# 1_STM32F103C8-core.net
KiCad netlist of a schematic drawn in Altium Designer
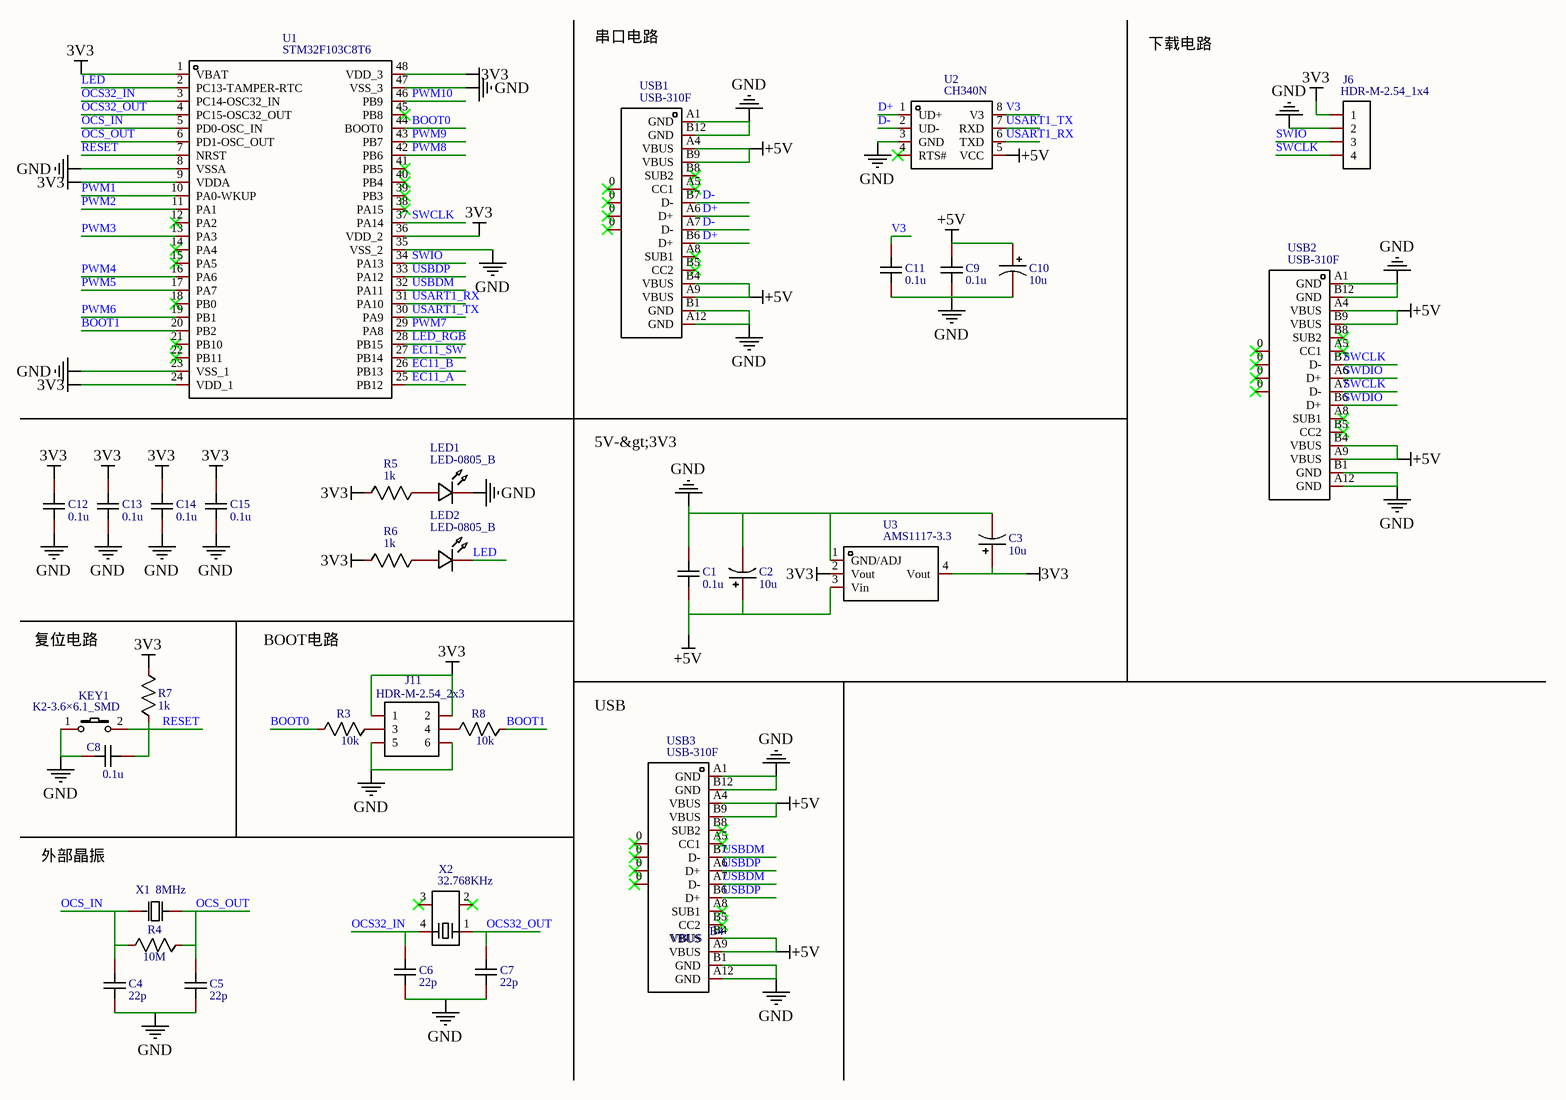
[diagram p0: 1_STM32F103C8-core.schdoc]

(export (version "E")
  (design (tool "Eeschema 10.0.6"))
  (components
    (comp (ref "C1")
      (value "0.1u")
      (fields (field (name "NAME") "0.1u"))
      (libsource (lib "altium-import") (part "root_1_0.1u_"))
    )
    (comp (ref "C2")
      (value "10u")
      (fields (field (name "NAME") "10u"))
      (libsource (lib "altium-import") (part "root_1_10u_"))
    )
    (comp (ref "C3")
      (value "10u")
      (fields (field (name "NAME") "10u"))
      (libsource (lib "altium-import") (part "root_1_10u_"))
    )
    (comp (ref "C4")
      (value "22p")
      (fields (field (name "NAME") "22p"))
      (libsource (lib "altium-import") (part "root_1_22p_"))
    )
    (comp (ref "C5")
      (value "22p")
      (fields (field (name "NAME") "22p"))
      (libsource (lib "altium-import") (part "root_1_22p_"))
    )
    (comp (ref "C6")
      (value "22p")
      (fields (field (name "NAME") "22p"))
      (libsource (lib "altium-import") (part "root_1_22p_"))
    )
    (comp (ref "C7")
      (value "22p")
      (fields (field (name "NAME") "22p"))
      (libsource (lib "altium-import") (part "root_1_22p_"))
    )
    (comp (ref "C8")
      (value "0.1u")
      (fields (field (name "NAME") "0.1u"))
      (libsource (lib "altium-import") (part "root_2_0.1u_"))
    )
    (comp (ref "C9")
      (value "0.1u")
      (fields (field (name "NAME") "0.1u"))
      (libsource (lib "altium-import") (part "root_1_0.1u_"))
    )
    (comp (ref "C10")
      (value "10u")
      (fields (field (name "NAME") "10u"))
      (libsource (lib "altium-import") (part "root_3_10u_"))
    )
    (comp (ref "C11")
      (value "0.1u")
      (fields (field (name "NAME") "0.1u"))
      (libsource (lib "altium-import") (part "root_1_0.1u_"))
    )
    (comp (ref "C12")
      (value "0.1u")
      (fields (field (name "NAME") "0.1u"))
      (libsource (lib "altium-import") (part "root_1_0.1u_"))
    )
    (comp (ref "C13")
      (value "0.1u")
      (fields (field (name "NAME") "0.1u"))
      (libsource (lib "altium-import") (part "root_1_0.1u_"))
    )
    (comp (ref "C14")
      (value "0.1u")
      (fields (field (name "NAME") "0.1u"))
      (libsource (lib "altium-import") (part "root_1_0.1u_"))
    )
    (comp (ref "C15")
      (value "0.1u")
      (fields (field (name "NAME") "0.1u"))
      (libsource (lib "altium-import") (part "root_1_0.1u_"))
    )
    (comp (ref "J6")
      (value "HDR-M-2.54_1x4")
      (fields (field (name "NAME") "HDR-M-2.54_1x4"))
      (libsource (lib "altium-import") (part "root_0_HDR-M-2.54_1x4_"))
    )
    (comp (ref "J11")
      (value "HDR-M-2.54_2x3")
      (fields (field (name "NAME") "HDR-M-2.54_2x3"))
      (libsource (lib "altium-import") (part "root_0_HDR-M-2.54_2x3_"))
    )
    (comp (ref "KEY1")
      (value "K2-3.6×6.1_SMD")
      (fields (field (name "NAME") "K2-3.6×6.1_SMD") (field (name "MANUFACTURER PART") "K2-1107ST-A4SW-06"))
      (libsource (lib "altium-import") (part "root_0_K2-1107ST-A4SW-06_"))
    )
    (comp (ref "LED1")
      (value "LED-0805_B")
      (fields
        (field (name "NAME") "LED-0805_B")
        (field (name "MANUFACTURER") "方舟 ARKLED")
        (field (name "MANUFACTURER PART") "D-B080508B1-KS2")
      )
      (libsource (lib "altium-import") (part "root_0_D-B080508B1-KS2_"))
    )
    (comp (ref "LED2")
      (value "LED-0805_B")
      (fields
        (field (name "NAME") "LED-0805_B")
        (field (name "MANUFACTURER") "方舟 ARKLED")
        (field (name "MANUFACTURER PART") "D-B080508B1-KS2")
      )
      (libsource (lib "altium-import") (part "root_0_D-B080508B1-KS2_"))
    )
    (comp (ref "R3")
      (value "10k")
      (fields (field (name "NAME") "10k"))
      (libsource (lib "altium-import") (part "root_0_10k_"))
    )
    (comp (ref "R4")
      (value "10M")
      (fields (field (name "NAME") "10M"))
      (libsource (lib "altium-import") (part "root_0_10M_"))
    )
    (comp (ref "R5")
      (value "1k")
      (fields (field (name "NAME") "1k"))
      (libsource (lib "altium-import") (part "root_0_1k_"))
    )
    (comp (ref "R6")
      (value "1k")
      (fields (field (name "NAME") "1k"))
      (libsource (lib "altium-import") (part "root_0_1k_"))
    )
    (comp (ref "R7")
      (value "1k")
      (fields (field (name "NAME") "1k"))
      (libsource (lib "altium-import") (part "root_1_1k_"))
    )
    (comp (ref "R8")
      (value "10k")
      (fields (field (name "NAME") "10k"))
      (libsource (lib "altium-import") (part "root_0_10k_"))
    )
    (comp (ref "U1")
      (value "STM32F103C8T6")
      (fields (field (name "NAME") "STM32F103C8T6") (field (name "MANUFACTURER") "STMicroelectronics"))
      (libsource (lib "altium-import") (part "root_0_STM32F103C8T6_"))
    )
    (comp (ref "U2")
      (value "CH340N")
      (fields (field (name "NAME") "CH340N"))
      (libsource (lib "altium-import") (part "root_0_CH340N_"))
    )
    (comp (ref "U3")
      (value "AMS1117-3.3")
      (fields (field (name "NAME") "AMS1117-3.3") (field (name "MANUFACTURER") "AMS"))
      (libsource (lib "altium-import") (part "root_0_AMS1117-3.3_"))
    )
    (comp (ref "USB1")
      (value "USB-310F")
      (fields (field (name "NAME") "USB-310F") (field (name "MANUFACTURER") "HOOYA"))
      (libsource (lib "altium-import") (part "root_0_USB-310F_"))
    )
    (comp (ref "USB2")
      (value "USB-310F")
      (fields (field (name "NAME") "USB-310F") (field (name "MANUFACTURER") "HOOYA"))
      (libsource (lib "altium-import") (part "root_0_USB-310F_"))
    )
    (comp (ref "USB3")
      (value "USB-310F")
      (fields
        (field (name "NAME") "USB-310F")
        (field (name "MANUFACTURER") "HOOYA")
        (field (name "NUMBER") "B4")
        (field (name "NAME_1") "VBUS")
      )
      (libsource (lib "altium-import") (part "root_0_USB-310F_"))
    )
    (comp (ref "X1")
      (value "8MHz")
      (description "频率:8MHz;频率公差:±20ppm;频率稳定度:±30ppm;负载电容:16pF;")
      (fields
        (field (name "NAME") "8MHz")
        (field (name "MANUFACTURER") "JYJE(晶友嘉)")
        (field (name "MANUFACTURER PART") "S1C80000VWGAC")
      )
      (libsource (lib "altium-import") (part "root_0_S1C80000VWGAC_"))
    )
    (comp (ref "X2")
      (value "32.768KHz")
      (fields
        (field (name "NAME") "32.768KHz")
        (field (name "MANUFACTURER PART") "Q13MC3061000300")
        (field (name "MANUFACTURER") "EPSON")
      )
      (libsource (lib "altium-import") (part "root_1_Q13MC3061000300_"))
    )
  )
  (nets
    (net (code "1") (name "+5V") (class "Default")
      (node (ref "C1") (pin "1") (pinfunction "1_1") (pintype "passive"))
      (node (ref "C10") (pin "1") (pinfunction "1_1") (pintype "passive"))
      (node (ref "C2") (pin "1") (pinfunction "1_1") (pintype "passive"))
      (node (ref "C9") (pin "2") (pinfunction "2_2") (pintype "passive"))
      (node (ref "U2") (pin "5") (pinfunction "VCC_5") (pintype "passive"))
      (node (ref "U3") (pin "3") (pinfunction "Vin_3") (pintype "passive"))
      (node (ref "USB1") (pin "A4") (pinfunction "VBUS_A4") (pintype "passive"))
      (node (ref "USB1") (pin "A9") (pinfunction "VBUS_A9") (pintype "passive"))
      (node (ref "USB1") (pin "B4") (pinfunction "VBUS_B4") (pintype "passive"))
      (node (ref "USB1") (pin "B9") (pinfunction "VBUS_B9") (pintype "passive"))
      (node (ref "USB2") (pin "A4") (pinfunction "VBUS_A4") (pintype "passive"))
      (node (ref "USB2") (pin "A9") (pinfunction "VBUS_A9") (pintype "passive"))
      (node (ref "USB2") (pin "B4") (pinfunction "VBUS_B4") (pintype "passive"))
      (node (ref "USB2") (pin "B9") (pinfunction "VBUS_B9") (pintype "passive"))
      (node (ref "USB3") (pin "A4") (pinfunction "VBUS_A4") (pintype "passive"))
      (node (ref "USB3") (pin "A9") (pinfunction "VBUS_A9") (pintype "passive"))
      (node (ref "USB3") (pin "B4") (pinfunction "VBUS_B4") (pintype "passive"))
      (node (ref "USB3") (pin "B9") (pinfunction "VBUS_B9") (pintype "passive"))
    )
    (net (code "2") (name "/BOOT0") (class "Default")
      (node (ref "R3") (pin "1") (pinfunction "1_1") (pintype "passive"))
      (node (ref "U1") (pin "44") (pinfunction "BOOT0_44") (pintype "passive"))
    )
    (net (code "3") (name "/BOOT1") (class "Default")
      (node (ref "R8") (pin "2") (pinfunction "2_2") (pintype "passive"))
      (node (ref "U1") (pin "20") (pinfunction "PB2_20") (pintype "passive"))
    )
    (net (code "4") (name "/D+") (class "Default")
      (node (ref "U2") (pin "1") (pinfunction "UD+_1") (pintype "passive"))
      (node (ref "USB1") (pin "A6") (pinfunction "D+_A6") (pintype "passive"))
      (node (ref "USB1") (pin "B6") (pinfunction "D+_B6") (pintype "passive"))
    )
    (net (code "5") (name "/D-") (class "Default")
      (node (ref "U2") (pin "2") (pinfunction "UD-_2") (pintype "passive"))
      (node (ref "USB1") (pin "A7") (pinfunction "D-_A7") (pintype "passive"))
      (node (ref "USB1") (pin "B7") (pinfunction "D-_B7") (pintype "passive"))
    )
    (net (code "6") (name "/EC11_A") (class "Default")
      (node (ref "U1") (pin "25") (pinfunction "PB12_25") (pintype "passive"))
    )
    (net (code "7") (name "/EC11_B") (class "Default")
      (node (ref "U1") (pin "26") (pinfunction "PB13_26") (pintype "passive"))
    )
    (net (code "8") (name "/EC11_SW") (class "Default")
      (node (ref "U1") (pin "27") (pinfunction "PB14_27") (pintype "passive"))
    )
    (net (code "9") (name "/LED") (class "Default")
      (node (ref "LED2") (pin "2") (pinfunction "2_2") (pintype "passive"))
      (node (ref "U1") (pin "2") (pinfunction "PC13-TAMPER-RTC_2") (pintype "passive"))
    )
    (net (code "10") (name "/LED_RGB") (class "Default")
      (node (ref "U1") (pin "28") (pinfunction "PB15_28") (pintype "passive"))
    )
    (net (code "11") (name "/OCS32_IN") (class "Default")
      (node (ref "C6") (pin "2") (pinfunction "2_2") (pintype "passive"))
      (node (ref "U1") (pin "3") (pinfunction "PC14-OSC32_IN_3") (pintype "passive"))
      (node (ref "X2") (pin "4") (pinfunction "4_4") (pintype "passive"))
    )
    (net (code "12") (name "/OCS32_OUT") (class "Default")
      (node (ref "C7") (pin "2") (pinfunction "2_2") (pintype "passive"))
      (node (ref "U1") (pin "4") (pinfunction "PC15-OSC32_OUT_4") (pintype "passive"))
      (node (ref "X2") (pin "1") (pinfunction "1_1") (pintype "passive"))
    )
    (net (code "13") (name "/OCS_IN") (class "Default")
      (node (ref "C4") (pin "2") (pinfunction "2_2") (pintype "passive"))
      (node (ref "R4") (pin "1") (pinfunction "1_1") (pintype "passive"))
      (node (ref "U1") (pin "5") (pinfunction "PD0-OSC_IN_5") (pintype "passive"))
      (node (ref "X1") (pin "1") (pinfunction "OSC1_1") (pintype "passive"))
    )
    (net (code "14") (name "/OCS_OUT") (class "Default")
      (node (ref "C5") (pin "2") (pinfunction "2_2") (pintype "passive"))
      (node (ref "R4") (pin "2") (pinfunction "2_2") (pintype "passive"))
      (node (ref "U1") (pin "6") (pinfunction "PD1-OSC_OUT_6") (pintype "passive"))
      (node (ref "X1") (pin "2") (pinfunction "OSC2_2") (pintype "passive"))
    )
    (net (code "15") (name "/PWM1") (class "Default")
      (node (ref "U1") (pin "10") (pinfunction "PA0-WKUP_10") (pintype "passive"))
    )
    (net (code "16") (name "/PWM2") (class "Default")
      (node (ref "U1") (pin "11") (pinfunction "PA1_11") (pintype "passive"))
    )
    (net (code "17") (name "/PWM3") (class "Default")
      (node (ref "U1") (pin "13") (pinfunction "PA3_13") (pintype "passive"))
    )
    (net (code "18") (name "/PWM4") (class "Default")
      (node (ref "U1") (pin "16") (pinfunction "PA6_16") (pintype "passive"))
    )
    (net (code "19") (name "/PWM5") (class "Default")
      (node (ref "U1") (pin "17") (pinfunction "PA7_17") (pintype "passive"))
    )
    (net (code "20") (name "/PWM6") (class "Default")
      (node (ref "U1") (pin "19") (pinfunction "PB1_19") (pintype "passive"))
    )
    (net (code "21") (name "/PWM7") (class "Default")
      (node (ref "U1") (pin "29") (pinfunction "PA8_29") (pintype "passive"))
    )
    (net (code "22") (name "/PWM8") (class "Default")
      (node (ref "U1") (pin "42") (pinfunction "PB6_42") (pintype "passive"))
    )
    (net (code "23") (name "/PWM9") (class "Default")
      (node (ref "U1") (pin "43") (pinfunction "PB7_43") (pintype "passive"))
    )
    (net (code "24") (name "/PWM10") (class "Default")
      (node (ref "U1") (pin "46") (pinfunction "PB9_46") (pintype "passive"))
    )
    (net (code "25") (name "/RESET") (class "Default")
      (node (ref "C8") (pin "1") (pinfunction "1_1") (pintype "passive"))
      (node (ref "KEY1") (pin "2") (pinfunction "2_2") (pintype "passive"))
      (node (ref "R7") (pin "1") (pinfunction "1_1") (pintype "passive"))
      (node (ref "U1") (pin "7") (pinfunction "NRST_7") (pintype "passive"))
    )
    (net (code "26") (name "/SWCLK") (class "Default")
      (node (ref "J6") (pin "4") (pinfunction "4_4") (pintype "passive"))
      (node (ref "U1") (pin "37") (pinfunction "PA14_37") (pintype "passive"))
      (node (ref "USB2") (pin "A7") (pinfunction "D-_A7") (pintype "passive"))
      (node (ref "USB2") (pin "B7") (pinfunction "D-_B7") (pintype "passive"))
    )
    (net (code "27") (name "/SWDIO") (class "Default")
      (node (ref "USB2") (pin "A6") (pinfunction "D+_A6") (pintype "passive"))
      (node (ref "USB2") (pin "B6") (pinfunction "D+_B6") (pintype "passive"))
    )
    (net (code "28") (name "/SWIO") (class "Default")
      (node (ref "J6") (pin "3") (pinfunction "3_3") (pintype "passive"))
      (node (ref "U1") (pin "34") (pinfunction "PA13_34") (pintype "passive"))
    )
    (net (code "29") (name "/USART1_RX") (class "Default")
      (node (ref "U1") (pin "31") (pinfunction "PA10_31") (pintype "passive"))
      (node (ref "U2") (pin "6") (pinfunction "TXD_6") (pintype "passive"))
    )
    (net (code "30") (name "/USART1_TX") (class "Default")
      (node (ref "U1") (pin "30") (pinfunction "PA9_30") (pintype "passive"))
      (node (ref "U2") (pin "7") (pinfunction "RXD_7") (pintype "passive"))
    )
    (net (code "31") (name "/USBDM") (class "Default")
      (node (ref "U1") (pin "32") (pinfunction "PA11_32") (pintype "passive"))
      (node (ref "USB3") (pin "A7") (pinfunction "D-_A7") (pintype "passive"))
      (node (ref "USB3") (pin "B7") (pinfunction "D-_B7") (pintype "passive"))
    )
    (net (code "32") (name "/USBDP") (class "Default")
      (node (ref "U1") (pin "33") (pinfunction "PA12_33") (pintype "passive"))
      (node (ref "USB3") (pin "A6") (pinfunction "D+_A6") (pintype "passive"))
      (node (ref "USB3") (pin "B6") (pinfunction "D+_B6") (pintype "passive"))
    )
    (net (code "33") (name "/V3") (class "Default")
      (node (ref "C11") (pin "2") (pinfunction "2_2") (pintype "passive"))
      (node (ref "U2") (pin "8") (pinfunction "V3_8") (pintype "passive"))
    )
    (net (code "34") (name "3V3") (class "Default")
      (node (ref "C12") (pin "2") (pinfunction "2_2") (pintype "passive"))
      (node (ref "C13") (pin "2") (pinfunction "2_2") (pintype "passive"))
      (node (ref "C14") (pin "2") (pinfunction "2_2") (pintype "passive"))
      (node (ref "C15") (pin "2") (pinfunction "2_2") (pintype "passive"))
      (node (ref "C3") (pin "1") (pinfunction "1_1") (pintype "passive"))
      (node (ref "J11") (pin "1") (pinfunction "1_1") (pintype "passive"))
      (node (ref "J11") (pin "2") (pinfunction "2_2") (pintype "passive"))
      (node (ref "J6") (pin "1") (pinfunction "1_1") (pintype "passive"))
      (node (ref "R5") (pin "1") (pinfunction "1_1") (pintype "passive"))
      (node (ref "R6") (pin "1") (pinfunction "1_1") (pintype "passive"))
      (node (ref "R7") (pin "2") (pinfunction "2_2") (pintype "passive"))
      (node (ref "U1") (pin "1") (pinfunction "VBAT_1") (pintype "passive"))
      (node (ref "U1") (pin "24") (pinfunction "VDD_1_24") (pintype "passive"))
      (node (ref "U1") (pin "36") (pinfunction "VDD_2_36") (pintype "passive"))
      (node (ref "U1") (pin "48") (pinfunction "VDD_3_48") (pintype "passive"))
      (node (ref "U1") (pin "9") (pinfunction "VDDA_9") (pintype "passive"))
      (node (ref "U3") (pin "2") (pinfunction "Vout_2") (pintype "passive"))
      (node (ref "U3") (pin "4") (pinfunction "Vout_4") (pintype "passive"))
    )
    (net (code "35") (name "GND") (class "Default")
      (node (ref "C1") (pin "2") (pinfunction "2_2") (pintype "passive"))
      (node (ref "C10") (pin "2") (pinfunction "2_2") (pintype "passive"))
      (node (ref "C11") (pin "1") (pinfunction "1_1") (pintype "passive"))
      (node (ref "C12") (pin "1") (pinfunction "1_1") (pintype "passive"))
      (node (ref "C13") (pin "1") (pinfunction "1_1") (pintype "passive"))
      (node (ref "C14") (pin "1") (pinfunction "1_1") (pintype "passive"))
      (node (ref "C15") (pin "1") (pinfunction "1_1") (pintype "passive"))
      (node (ref "C2") (pin "2") (pinfunction "2_2") (pintype "passive"))
      (node (ref "C3") (pin "2") (pinfunction "2_2") (pintype "passive"))
      (node (ref "C4") (pin "1") (pinfunction "1_1") (pintype "passive"))
      (node (ref "C5") (pin "1") (pinfunction "1_1") (pintype "passive"))
      (node (ref "C6") (pin "1") (pinfunction "1_1") (pintype "passive"))
      (node (ref "C7") (pin "1") (pinfunction "1_1") (pintype "passive"))
      (node (ref "C8") (pin "2") (pinfunction "2_2") (pintype "passive"))
      (node (ref "C9") (pin "1") (pinfunction "1_1") (pintype "passive"))
      (node (ref "J11") (pin "5") (pinfunction "5_5") (pintype "passive"))
      (node (ref "J11") (pin "6") (pinfunction "6_6") (pintype "passive"))
      (node (ref "J6") (pin "2") (pinfunction "2_2") (pintype "passive"))
      (node (ref "KEY1") (pin "1") (pinfunction "1_1") (pintype "passive"))
      (node (ref "LED1") (pin "2") (pinfunction "2_2") (pintype "passive"))
      (node (ref "U1") (pin "23") (pinfunction "VSS_1_23") (pintype "passive"))
      (node (ref "U1") (pin "35") (pinfunction "VSS_2_35") (pintype "passive"))
      (node (ref "U1") (pin "47") (pinfunction "VSS_3_47") (pintype "passive"))
      (node (ref "U1") (pin "8") (pinfunction "VSSA_8") (pintype "passive"))
      (node (ref "U2") (pin "3") (pinfunction "GND_3") (pintype "passive"))
      (node (ref "U3") (pin "1") (pinfunction "GND/ADJ_1") (pintype "passive"))
      (node (ref "USB1") (pin "A1") (pinfunction "GND_A1") (pintype "passive"))
      (node (ref "USB1") (pin "A12") (pinfunction "GND_A12") (pintype "passive"))
      (node (ref "USB1") (pin "B1") (pinfunction "GND_B1") (pintype "passive"))
      (node (ref "USB1") (pin "B12") (pinfunction "GND_B12") (pintype "passive"))
      (node (ref "USB2") (pin "A1") (pinfunction "GND_A1") (pintype "passive"))
      (node (ref "USB2") (pin "A12") (pinfunction "GND_A12") (pintype "passive"))
      (node (ref "USB2") (pin "B1") (pinfunction "GND_B1") (pintype "passive"))
      (node (ref "USB2") (pin "B12") (pinfunction "GND_B12") (pintype "passive"))
      (node (ref "USB3") (pin "A1") (pinfunction "GND_A1") (pintype "passive"))
      (node (ref "USB3") (pin "A12") (pinfunction "GND_A12") (pintype "passive"))
      (node (ref "USB3") (pin "B1") (pinfunction "GND_B1") (pintype "passive"))
      (node (ref "USB3") (pin "B12") (pinfunction "GND_B12") (pintype "passive"))
    )
    (net (code "36") (name "Net-(J11-Pad3)") (class "Default")
      (node (ref "J11") (pin "3") (pinfunction "3_3") (pintype "passive"))
      (node (ref "R3") (pin "2") (pinfunction "2_2") (pintype "passive"))
    )
    (net (code "37") (name "Net-(J11-Pad4)") (class "Default")
      (node (ref "J11") (pin "4") (pinfunction "4_4") (pintype "passive"))
      (node (ref "R8") (pin "1") (pinfunction "1_1") (pintype "passive"))
    )
    (net (code "38") (name "Net-(LED1-Pad1)") (class "Default")
      (node (ref "LED1") (pin "1") (pinfunction "1_1") (pintype "passive"))
      (node (ref "R5") (pin "2") (pinfunction "2_2") (pintype "passive"))
    )
    (net (code "39") (name "Net-(LED2-Pad1)") (class "Default")
      (node (ref "LED2") (pin "1") (pinfunction "1_1") (pintype "passive"))
      (node (ref "R6") (pin "2") (pinfunction "2_2") (pintype "passive"))
    )
    (net (code "40") (name "unconnected-(U1-PA2-Pad12)") (class "Default")
      (node (ref "U1") (pin "12") (pinfunction "PA2_12") (pintype "passive+no_connect"))
    )
    (net (code "41") (name "unconnected-(U1-PA4-Pad14)") (class "Default")
      (node (ref "U1") (pin "14") (pinfunction "PA4_14") (pintype "passive+no_connect"))
    )
    (net (code "42") (name "unconnected-(U1-PA5-Pad15)") (class "Default")
      (node (ref "U1") (pin "15") (pinfunction "PA5_15") (pintype "passive+no_connect"))
    )
    (net (code "43") (name "unconnected-(U1-PA15-Pad38)") (class "Default")
      (node (ref "U1") (pin "38") (pinfunction "PA15_38") (pintype "passive+no_connect"))
    )
    (net (code "44") (name "unconnected-(U1-PB0-Pad18)") (class "Default")
      (node (ref "U1") (pin "18") (pinfunction "PB0_18") (pintype "passive+no_connect"))
    )
    (net (code "45") (name "unconnected-(U1-PB3-Pad39)") (class "Default")
      (node (ref "U1") (pin "39") (pinfunction "PB3_39") (pintype "passive+no_connect"))
    )
    (net (code "46") (name "unconnected-(U1-PB4-Pad40)") (class "Default")
      (node (ref "U1") (pin "40") (pinfunction "PB4_40") (pintype "passive+no_connect"))
    )
    (net (code "47") (name "unconnected-(U1-PB5-Pad41)") (class "Default")
      (node (ref "U1") (pin "41") (pinfunction "PB5_41") (pintype "passive+no_connect"))
    )
    (net (code "48") (name "unconnected-(U1-PB8-Pad45)") (class "Default")
      (node (ref "U1") (pin "45") (pinfunction "PB8_45") (pintype "passive+no_connect"))
    )
    (net (code "49") (name "unconnected-(U1-PB10-Pad21)") (class "Default")
      (node (ref "U1") (pin "21") (pinfunction "PB10_21") (pintype "passive+no_connect"))
    )
    (net (code "50") (name "unconnected-(U1-PB11-Pad22)") (class "Default")
      (node (ref "U1") (pin "22") (pinfunction "PB11_22") (pintype "passive+no_connect"))
    )
    (net (code "51") (name "unconnected-(U2-RTS#-Pad4)") (class "Default")
      (node (ref "U2") (pin "4") (pinfunction "RTS#_4") (pintype "passive+no_connect"))
    )
    (net (code "52") (name "unconnected-(USB1-CC1-PadA5)") (class "Default")
      (node (ref "USB1") (pin "A5") (pinfunction "CC1_A5") (pintype "passive+no_connect"))
    )
    (net (code "53") (name "unconnected-(USB1-CC2-PadB5)") (class "Default")
      (node (ref "USB1") (pin "B5") (pinfunction "CC2_B5") (pintype "passive+no_connect"))
    )
    (net (code "54") (name "unconnected-(USB1-Pad0)") (class "Default")
      (node (ref "USB1") (pin "0") (pinfunction "0_0") (pintype "passive+no_connect"))
    )
    (net (code "55") (name "unconnected-(USB1-Pad0)_1") (class "Default")
      (node (ref "USB1") (pin "0") (pinfunction "0_0") (pintype "passive+no_connect"))
    )
    (net (code "56") (name "unconnected-(USB1-Pad0)_2") (class "Default")
      (node (ref "USB1") (pin "0") (pinfunction "0_0") (pintype "passive+no_connect"))
    )
    (net (code "57") (name "unconnected-(USB1-Pad0)_3") (class "Default")
      (node (ref "USB1") (pin "0") (pinfunction "0_0") (pintype "passive+no_connect"))
    )
    (net (code "58") (name "unconnected-(USB1-SUB1-PadA8)") (class "Default")
      (node (ref "USB1") (pin "A8") (pinfunction "SUB1_A8") (pintype "passive+no_connect"))
    )
    (net (code "59") (name "unconnected-(USB1-SUB2-PadB8)") (class "Default")
      (node (ref "USB1") (pin "B8") (pinfunction "SUB2_B8") (pintype "passive+no_connect"))
    )
    (net (code "60") (name "unconnected-(USB2-CC1-PadA5)") (class "Default")
      (node (ref "USB2") (pin "A5") (pinfunction "CC1_A5") (pintype "passive+no_connect"))
    )
    (net (code "61") (name "unconnected-(USB2-CC2-PadB5)") (class "Default")
      (node (ref "USB2") (pin "B5") (pinfunction "CC2_B5") (pintype "passive+no_connect"))
    )
    (net (code "62") (name "unconnected-(USB2-Pad0)") (class "Default")
      (node (ref "USB2") (pin "0") (pinfunction "0_0") (pintype "passive+no_connect"))
    )
    (net (code "63") (name "unconnected-(USB2-Pad0)_1") (class "Default")
      (node (ref "USB2") (pin "0") (pinfunction "0_0") (pintype "passive+no_connect"))
    )
    (net (code "64") (name "unconnected-(USB2-Pad0)_2") (class "Default")
      (node (ref "USB2") (pin "0") (pinfunction "0_0") (pintype "passive+no_connect"))
    )
    (net (code "65") (name "unconnected-(USB2-Pad0)_3") (class "Default")
      (node (ref "USB2") (pin "0") (pinfunction "0_0") (pintype "passive+no_connect"))
    )
    (net (code "66") (name "unconnected-(USB2-SUB1-PadA8)") (class "Default")
      (node (ref "USB2") (pin "A8") (pinfunction "SUB1_A8") (pintype "passive+no_connect"))
    )
    (net (code "67") (name "unconnected-(USB2-SUB2-PadB8)") (class "Default")
      (node (ref "USB2") (pin "B8") (pinfunction "SUB2_B8") (pintype "passive+no_connect"))
    )
    (net (code "68") (name "unconnected-(USB3-CC1-PadA5)") (class "Default")
      (node (ref "USB3") (pin "A5") (pinfunction "CC1_A5") (pintype "passive+no_connect"))
    )
    (net (code "69") (name "unconnected-(USB3-CC2-PadB5)") (class "Default")
      (node (ref "USB3") (pin "B5") (pinfunction "CC2_B5") (pintype "passive+no_connect"))
    )
    (net (code "70") (name "unconnected-(USB3-Pad0)") (class "Default")
      (node (ref "USB3") (pin "0") (pinfunction "0_0") (pintype "passive+no_connect"))
    )
    (net (code "71") (name "unconnected-(USB3-Pad0)_1") (class "Default")
      (node (ref "USB3") (pin "0") (pinfunction "0_0") (pintype "passive+no_connect"))
    )
    (net (code "72") (name "unconnected-(USB3-Pad0)_2") (class "Default")
      (node (ref "USB3") (pin "0") (pinfunction "0_0") (pintype "passive+no_connect"))
    )
    (net (code "73") (name "unconnected-(USB3-Pad0)_3") (class "Default")
      (node (ref "USB3") (pin "0") (pinfunction "0_0") (pintype "passive+no_connect"))
    )
    (net (code "74") (name "unconnected-(USB3-SUB1-PadA8)") (class "Default")
      (node (ref "USB3") (pin "A8") (pinfunction "SUB1_A8") (pintype "passive+no_connect"))
    )
    (net (code "75") (name "unconnected-(USB3-SUB2-PadB8)") (class "Default")
      (node (ref "USB3") (pin "B8") (pinfunction "SUB2_B8") (pintype "passive+no_connect"))
    )
    (net (code "76") (name "unconnected-(X2-Pad2)") (class "Default")
      (node (ref "X2") (pin "2") (pinfunction "2_2") (pintype "passive+no_connect"))
    )
    (net (code "77") (name "unconnected-(X2-Pad3)") (class "Default")
      (node (ref "X2") (pin "3") (pinfunction "3_3") (pintype "passive+no_connect"))
    )
  )
)
